# CW308_IMXRT1062_UFO.net
KiCad netlist of a schematic drawn in Altium Designer
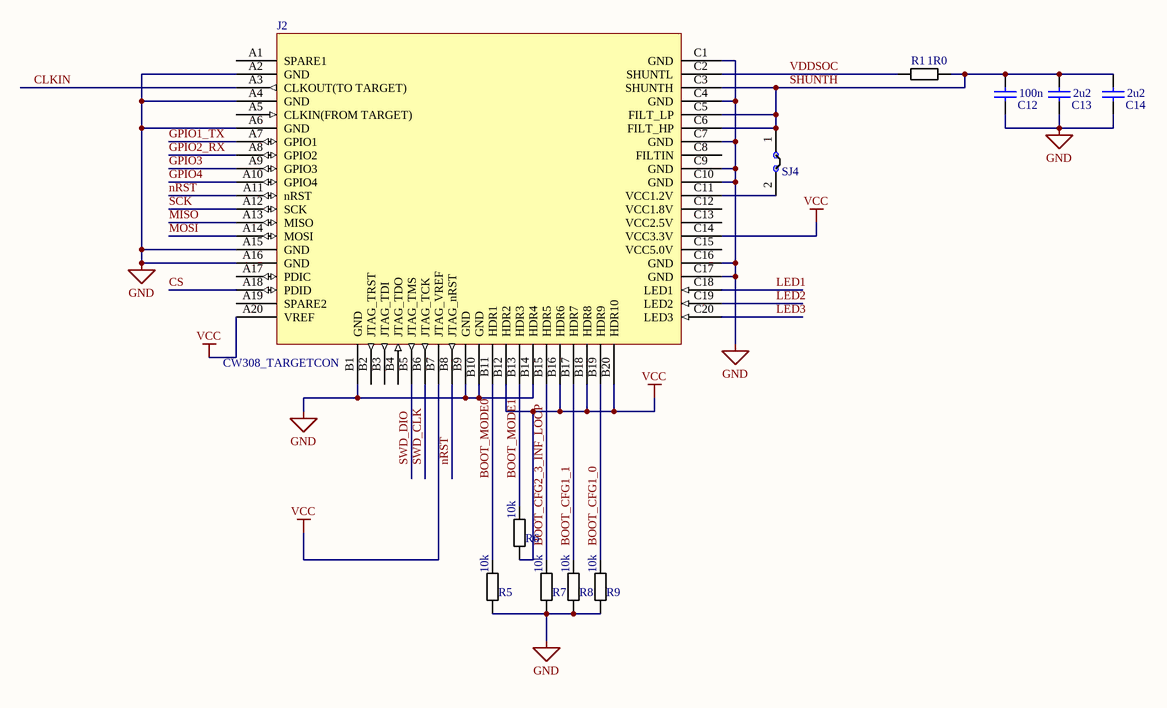
[diagram p0: CW308_IMXRT1062_UFO.SchDoc]

(export (version "E")
  (design (tool "Eeschema 10.0.6"))
  (components
    (comp (ref "C12")
      (value "100n")
      (footprint "CAPC0603_M")
      (description "100n, 0603")
      (fields (field (name "PART NUMBER") "CCHIP-100n-0603"))
      (libsource (lib "NewAE_AltiumLib") (part "CAP"))
    )
    (comp (ref "C13")
      (value "2u2")
      (footprint "CAPC0603_M")
      (description "2u2, 0603")
      (fields (field (name "PART NUMBER") "CCHIP-2u2-0603"))
      (libsource (lib "NewAE_AltiumLib") (part "CAP"))
    )
    (comp (ref "C14")
      (value "2u2")
      (footprint "CAPC0603_M")
      (description "2u2, 0603")
      (fields (field (name "PART NUMBER") "CCHIP-2u2-0603"))
      (libsource (lib "NewAE_AltiumLib") (part "CAP"))
    )
    (comp (ref "J2")
      (value "CW308_TARGETCON")
      (footprint "CW308_TBOARD_CONN")
      (description "CW308 \"Standard\" Target Board Connector")
      (fields (field (name "PART NUMBER") "CW308_TBOARD"))
      (libsource (lib "NewAE_AltiumLib") (part "CW308_TBOARD"))
    )
    (comp (ref "R1")
      (value "1R0")
      (footprint "RESC1608X55N")
      (description "1R0 res, 0603, 1%, 1/10W")
      (fields (field (name "PART NUMBER") "RCHIP-1R0-0603") (field (name "TOLERANCE") "1%"))
      (libsource (lib "") (part "RES-EU_2"))
    )
    (comp (ref "R5")
      (value "10k")
      (footprint "RESC1608X55N")
      (description "10k res, 0603, 1%, 1/10W")
      (fields (field (name "PART NUMBER") "RCHIP-10K-0603") (field (name "TOLERANCE") "1%"))
      (libsource (lib "NewAE_AltiumLib") (part "RES-EU"))
    )
    (comp (ref "R6")
      (value "10k")
      (footprint "RESC1608X55N")
      (description "10k res, 0603, 1%, 1/10W")
      (fields (field (name "PART NUMBER") "RCHIP-10K-0603") (field (name "TOLERANCE") "1%"))
      (libsource (lib "NewAE_AltiumLib") (part "RES-EU"))
    )
    (comp (ref "R7")
      (value "10k")
      (footprint "RESC1608X55N")
      (description "10k res, 0603, 1%, 1/10W")
      (fields (field (name "PART NUMBER") "RCHIP-10K-0603") (field (name "TOLERANCE") "1%"))
      (libsource (lib "NewAE_AltiumLib") (part "RES-EU"))
    )
    (comp (ref "R8")
      (value "10k")
      (footprint "RESC1608X55N")
      (description "10k res, 0603, 1%, 1/10W")
      (fields (field (name "PART NUMBER") "RCHIP-10K-0603") (field (name "TOLERANCE") "1%"))
      (libsource (lib "NewAE_AltiumLib") (part "RES-EU"))
    )
    (comp (ref "R9")
      (value "10k")
      (footprint "RESC1608X55N")
      (description "10k res, 0603, 1%, 1/10W")
      (fields (field (name "PART NUMBER") "RCHIP-10K-0603") (field (name "TOLERANCE") "1%"))
      (libsource (lib "") (part "RES-EU_1"))
    )
    (comp (ref "SJ4")
      (value "NC")
      (footprint "SJ_2S_NC")
      (description "Solder Jumper, NC")
      (fields (field (name "PART NUMBER") "SJ_2S"))
      (libsource (lib "NewAE_AltiumLib") (part "SJ_2S"))
    )
  )
  (nets
    (net (code "1") (name "/BOOT_CFG1_0") (class "Default")
      (node (ref "J2") (pin "B19") (pinfunction "HDR9_B19") (pintype "passive"))
      (node (ref "R9") (pin "2") (pinfunction "2_2") (pintype "passive"))
    )
    (net (code "2") (name "/BOOT_CFG1_1") (class "Default")
      (node (ref "J2") (pin "B17") (pinfunction "HDR7_B17") (pintype "passive"))
      (node (ref "R8") (pin "1") (pinfunction "1_1") (pintype "passive"))
    )
    (net (code "3") (name "/BOOT_CFG2_3_INF_LOOP") (class "Default")
      (node (ref "J2") (pin "B15") (pinfunction "HDR5_B15") (pintype "passive"))
      (node (ref "R7") (pin "1") (pinfunction "1_1") (pintype "passive"))
    )
    (net (code "4") (name "/BOOT_MODE0") (class "Default")
      (node (ref "J2") (pin "B11") (pinfunction "HDR1_B11") (pintype "passive"))
      (node (ref "R5") (pin "1") (pinfunction "1_1") (pintype "passive"))
    )
    (net (code "5") (name "/BOOT_MODE1") (class "Default")
      (node (ref "J2") (pin "B13") (pinfunction "HDR3_B13") (pintype "passive"))
      (node (ref "R6") (pin "1") (pinfunction "1_1") (pintype "passive"))
    )
    (net (code "6") (name "/CLKIN") (class "Default")
      (node (ref "J2") (pin "A3") (pinfunction "CLKOUT(TO_TARGET)_A3") (pintype "output"))
    )
    (net (code "7") (name "/CS") (class "Default")
      (node (ref "J2") (pin "A18") (pinfunction "PDID_A18") (pintype "bidirectional"))
    )
    (net (code "8") (name "/GPIO1_TX") (class "Default")
      (node (ref "J2") (pin "A7") (pinfunction "GPIO1_A7") (pintype "bidirectional"))
    )
    (net (code "9") (name "/GPIO2_RX") (class "Default")
      (node (ref "J2") (pin "A8") (pinfunction "GPIO2_A8") (pintype "bidirectional"))
    )
    (net (code "10") (name "/GPIO3") (class "Default")
      (node (ref "J2") (pin "A9") (pinfunction "GPIO3_A9") (pintype "bidirectional"))
    )
    (net (code "11") (name "/GPIO4") (class "Default")
      (node (ref "J2") (pin "A10") (pinfunction "GPIO4_A10") (pintype "bidirectional"))
    )
    (net (code "12") (name "/LED1") (class "Default")
      (node (ref "J2") (pin "C18") (pinfunction "LED1_C18") (pintype "input"))
    )
    (net (code "13") (name "/LED2") (class "Default")
      (node (ref "J2") (pin "C19") (pinfunction "LED2_C19") (pintype "input"))
    )
    (net (code "14") (name "/LED3") (class "Default")
      (node (ref "J2") (pin "C20") (pinfunction "LED3_C20") (pintype "input"))
    )
    (net (code "15") (name "/MISO") (class "Default")
      (node (ref "J2") (pin "A13") (pinfunction "MISO_A13") (pintype "bidirectional"))
    )
    (net (code "16") (name "/MOSI") (class "Default")
      (node (ref "J2") (pin "A14") (pinfunction "MOSI_A14") (pintype "bidirectional"))
    )
    (net (code "17") (name "/SCK") (class "Default")
      (node (ref "J2") (pin "A12") (pinfunction "SCK_A12") (pintype "bidirectional"))
    )
    (net (code "18") (name "/SHUNTH") (class "Default")
      (node (ref "C12") (pin "1") (pinfunction "1_1") (pintype "passive"))
      (node (ref "C13") (pin "1") (pinfunction "1_1") (pintype "passive"))
      (node (ref "C14") (pin "1") (pinfunction "1_1") (pintype "passive"))
      (node (ref "J2") (pin "C3") (pinfunction "SHUNTH_C3") (pintype "passive"))
      (node (ref "J2") (pin "C5") (pinfunction "FILT_LP_C5") (pintype "passive"))
      (node (ref "J2") (pin "C6") (pinfunction "FILT_HP_C6") (pintype "passive"))
      (node (ref "R1") (pin "2") (pinfunction "2_2") (pintype "passive"))
      (node (ref "SJ4") (pin "1") (pinfunction "1_1") (pintype "passive"))
    )
    (net (code "19") (name "/SWD_CLK") (class "Default")
      (node (ref "J2") (pin "B6") (pinfunction "JTAG_TCK_B6") (pintype "output"))
    )
    (net (code "20") (name "/SWD_DIO") (class "Default")
      (node (ref "J2") (pin "B5") (pinfunction "JTAG_TMS_B5") (pintype "output"))
    )
    (net (code "21") (name "/VDDSOC") (class "Default")
      (node (ref "J2") (pin "C2") (pinfunction "SHUNTL_C2") (pintype "passive"))
      (node (ref "R1") (pin "1") (pinfunction "1_1") (pintype "passive"))
    )
    (net (code "22") (name "/nRST") (class "Default")
      (node (ref "J2") (pin "A11") (pinfunction "nRST_A11") (pintype "bidirectional"))
      (node (ref "J2") (pin "B8") (pinfunction "JTAG_nRST_B8") (pintype "output"))
    )
    (net (code "23") (name "GND") (class "Default")
      (node (ref "C12") (pin "2") (pinfunction "2_2") (pintype "passive"))
      (node (ref "C13") (pin "2") (pinfunction "2_2") (pintype "passive"))
      (node (ref "C14") (pin "2") (pinfunction "2_2") (pintype "passive"))
      (node (ref "J2") (pin "A15") (pinfunction "GND_A15") (pintype "passive"))
      (node (ref "J2") (pin "A16") (pinfunction "GND_A16") (pintype "passive"))
      (node (ref "J2") (pin "A2") (pinfunction "GND_A2") (pintype "passive"))
      (node (ref "J2") (pin "A4") (pinfunction "GND_A4") (pintype "passive"))
      (node (ref "J2") (pin "A6") (pinfunction "GND_A6") (pintype "power_in"))
      (node (ref "J2") (pin "B1") (pinfunction "GND_B1") (pintype "passive"))
      (node (ref "J2") (pin "B10") (pinfunction "GND_B10") (pintype "passive"))
      (node (ref "J2") (pin "B14") (pinfunction "HDR4_B14") (pintype "passive"))
      (node (ref "J2") (pin "B9") (pinfunction "GND_B9") (pintype "passive"))
      (node (ref "J2") (pin "C1") (pinfunction "GND_C1") (pintype "power_in"))
      (node (ref "J2") (pin "C10") (pinfunction "GND_C10") (pintype "power_in"))
      (node (ref "J2") (pin "C16") (pinfunction "GND_C16") (pintype "power_in"))
      (node (ref "J2") (pin "C17") (pinfunction "GND_C17") (pintype "power_in"))
      (node (ref "J2") (pin "C4") (pinfunction "GND_C4") (pintype "power_in"))
      (node (ref "J2") (pin "C7") (pinfunction "GND_C7") (pintype "power_in"))
      (node (ref "J2") (pin "C9") (pinfunction "GND_C9") (pintype "power_in"))
      (node (ref "R5") (pin "2") (pinfunction "2_2") (pintype "passive"))
      (node (ref "R7") (pin "2") (pinfunction "2_2") (pintype "passive"))
      (node (ref "R8") (pin "2") (pinfunction "2_2") (pintype "passive"))
      (node (ref "R9") (pin "1") (pinfunction "1_1") (pintype "passive"))
    )
    (net (code "24") (name "Net-(J2-VCC1.2V)") (class "Default")
      (node (ref "J2") (pin "C11") (pinfunction "VCC1.2V_C11") (pintype "power_in"))
      (node (ref "SJ4") (pin "2") (pinfunction "2_2") (pintype "passive"))
    )
    (net (code "25") (name "VCC") (class "Default")
      (node (ref "J2") (pin "A20") (pinfunction "VREF_A20") (pintype "tri_state"))
      (node (ref "J2") (pin "B12") (pinfunction "HDR2_B12") (pintype "passive"))
      (node (ref "J2") (pin "B16") (pinfunction "HDR6_B16") (pintype "passive"))
      (node (ref "J2") (pin "B18") (pinfunction "HDR8_B18") (pintype "passive"))
      (node (ref "J2") (pin "B20") (pinfunction "HDR10_B20") (pintype "passive"))
      (node (ref "J2") (pin "B7") (pinfunction "JTAG_VREF_B7") (pintype "tri_state"))
      (node (ref "J2") (pin "C14") (pinfunction "VCC3.3V_C14") (pintype "power_in"))
      (node (ref "R6") (pin "2") (pinfunction "2_2") (pintype "passive"))
    )
    (net (code "26") (name "unconnected-(J2-CLKIN(FROM_TARGET)-PadA5)") (class "Default")
      (node (ref "J2") (pin "A5") (pinfunction "CLKIN(FROM_TARGET)_A5") (pintype "input"))
    )
    (net (code "27") (name "unconnected-(J2-FILTIN-PadC8)") (class "Default")
      (node (ref "J2") (pin "C8") (pinfunction "FILTIN_C8") (pintype "passive"))
    )
    (net (code "28") (name "unconnected-(J2-JTAG_TDI-PadB3)") (class "Default")
      (node (ref "J2") (pin "B3") (pinfunction "JTAG_TDI_B3") (pintype "output"))
    )
    (net (code "29") (name "unconnected-(J2-JTAG_TDO-PadB4)") (class "Default")
      (node (ref "J2") (pin "B4") (pinfunction "JTAG_TDO_B4") (pintype "input"))
    )
    (net (code "30") (name "unconnected-(J2-JTAG_TRST-PadB2)") (class "Default")
      (node (ref "J2") (pin "B2") (pinfunction "JTAG_TRST_B2") (pintype "output"))
    )
    (net (code "31") (name "unconnected-(J2-PDIC-PadA17)") (class "Default")
      (node (ref "J2") (pin "A17") (pinfunction "PDIC_A17") (pintype "bidirectional"))
    )
    (net (code "32") (name "unconnected-(J2-SPARE1-PadA1)") (class "Default")
      (node (ref "J2") (pin "A1") (pinfunction "SPARE1_A1") (pintype "passive"))
    )
    (net (code "33") (name "unconnected-(J2-SPARE2-PadA19)") (class "Default")
      (node (ref "J2") (pin "A19") (pinfunction "SPARE2_A19") (pintype "passive"))
    )
    (net (code "34") (name "unconnected-(J2-VCC1.8V-PadC12)") (class "Default")
      (node (ref "J2") (pin "C12") (pinfunction "VCC1.8V_C12") (pintype "power_in"))
    )
    (net (code "35") (name "unconnected-(J2-VCC2.5V-PadC13)") (class "Default")
      (node (ref "J2") (pin "C13") (pinfunction "VCC2.5V_C13") (pintype "power_in"))
    )
    (net (code "36") (name "unconnected-(J2-VCC5.0V-PadC15)") (class "Default")
      (node (ref "J2") (pin "C15") (pinfunction "VCC5.0V_C15") (pintype "power_in"))
    )
  )
)
